# 14V2A.net
KiCad netlist of a schematic drawn in Altium Designer
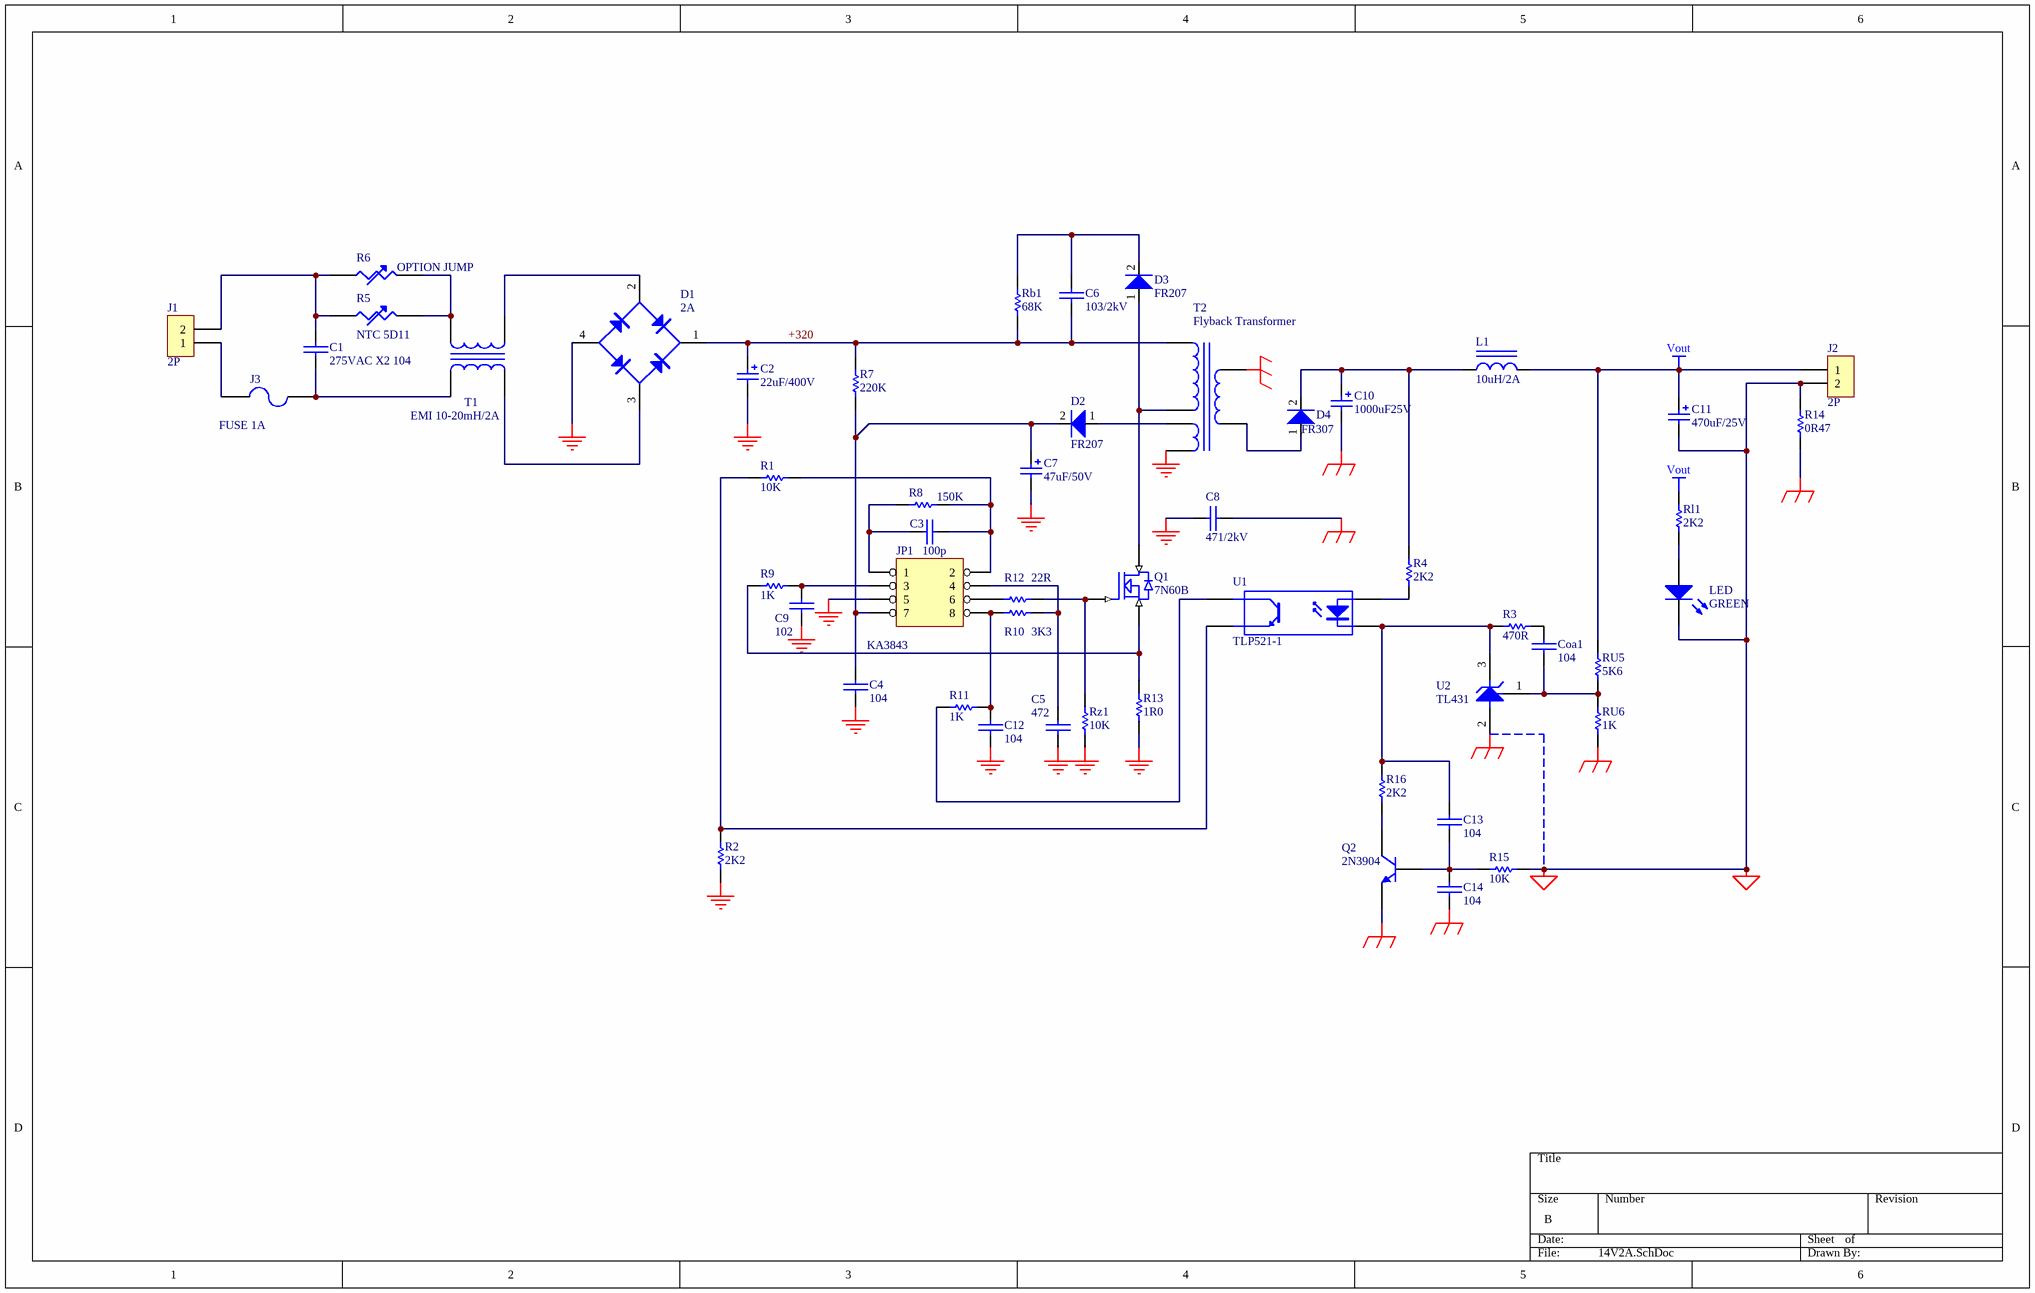
[diagram p0: 14V2A.SchDoc]

(export (version "E")
  (design (tool "Eeschema 10.0.6"))
  (components
    (comp (ref "C1")
      (value "275VAC X2 104")
      (footprint "100N400v")
      (fields (field (name "Comment") "Tụ điện chân cắm275VAC X2 104"))
      (libsource (lib "DnsSchLib") (part "CAP"))
    )
    (comp (ref "C2")
      (value "22uF/400V")
      (footprint "1000u50v")
      (description "Polarized Capacitor (Radial)")
      (fields (field (name "Comment") "Tụ hóa chân cắm22uF/400V") (field (name "PUBLISHER") "*"))
      (libsource (lib "DnsSchLib") (part "Cap Pol1"))
    )
    (comp (ref "C3")
      (value "100p")
      (footprint "0805C")
      (fields (field (name "Comment") "Tụ điện dán 0805100p"))
      (libsource (lib "DnsSchLib") (part "CAP"))
    )
    (comp (ref "C4")
      (value "104")
      (footprint "0805C")
      (fields (field (name "Comment") "Tụ điện dán 0805104"))
      (libsource (lib "DnsSchLib") (part "CAP"))
    )
    (comp (ref "C5")
      (value "472")
      (footprint "104nho")
      (fields (field (name "Comment") "Tụ điện chân cắm472"))
      (libsource (lib "DnsSchLib") (part "CAP"))
    )
    (comp (ref "C6")
      (value "103/2kV")
      (footprint "10n1000v")
      (fields (field (name "Comment") "Tụ điện chân cắm103/2kV"))
      (libsource (lib "DnsSchLib") (part "CAP"))
    )
    (comp (ref "C7")
      (value "47uF/50V")
      (footprint "10u50V")
      (description "Polarized Capacitor (Radial)")
      (fields (field (name "Comment") "Tụ hóa chân cắm47uF/50V") (field (name "PUBLISHER") "*"))
      (libsource (lib "DnsSchLib") (part "Cap Pol1"))
    )
    (comp (ref "C8")
      (value "471/2kV")
      (footprint "10n1000v")
      (fields (field (name "Comment") "Tụ điện chân cắm471/2kV"))
      (libsource (lib "DnsSchLib") (part "CAP"))
    )
    (comp (ref "C9")
      (value "102")
      (footprint "0805C")
      (fields (field (name "Comment") "Tụ điện dán 0805102"))
      (libsource (lib "DnsSchLib") (part "CAP"))
    )
    (comp (ref "C10")
      (value "1000uF25V")
      (footprint "1000u16v")
      (description "Polarized Capacitor (Radial)")
      (fields (field (name "Comment") "Tụ hóa chân cắm1000uF25V") (field (name "PUBLISHER") "*"))
      (libsource (lib "DnsSchLib") (part "Cap Pol1"))
    )
    (comp (ref "C11")
      (value "470uF/25V")
      (footprint "1000u16v")
      (description "Polarized Capacitor (Radial)")
      (fields (field (name "Comment") "Tụ hóa chân cắm470uF/25V") (field (name "PUBLISHER") "*"))
      (libsource (lib "DnsSchLib") (part "Cap Pol1"))
    )
    (comp (ref "C12")
      (value "104")
      (footprint "0805C")
      (fields (field (name "Comment") "Tụ điện dán 0805104"))
      (libsource (lib "DnsSchLib") (part "CAP"))
    )
    (comp (ref "C13")
      (value "104")
      (footprint "0805C")
      (fields (field (name "Comment") "Tụ điện dán 0805104"))
      (libsource (lib "DnsSchLib") (part "CAP"))
    )
    (comp (ref "C14")
      (value "104")
      (footprint "0805C")
      (fields (field (name "Comment") "Tụ điện dán 0805104"))
      (libsource (lib "DnsSchLib") (part "CAP"))
    )
    (comp (ref "Coa1")
      (value "104")
      (footprint "0805C")
      (fields (field (name "Comment") "Tụ điện dán 0805104"))
      (libsource (lib "DnsSchLib") (part "CAP"))
    )
    (comp (ref "D1")
      (value "2A")
      (footprint "Cau2a")
      (description "Diode Bridge")
      (fields (field (name "Comment") "Cầu chỉnh lưu Diode dẹt, chân cắm2A"))
      (libsource (lib "DnsSchLib") (part "BRIDGE1"))
    )
    (comp (ref "D2")
      (value "FR207")
      (footprint "DIODE1A")
      (fields (field (name "Comment") "Diode xung chân cắm 2AFR207"))
      (libsource (lib "DnsSchLib") (part "DIODE"))
    )
    (comp (ref "D3")
      (value "FR207")
      (footprint "DIODE1A")
      (fields (field (name "Comment") "Diode xung chân cắm 2AFR207"))
      (libsource (lib "DnsSchLib") (part "DIODE"))
    )
    (comp (ref "D4")
      (value "FR307")
      (footprint "1N5408")
      (fields (field (name "Comment") "Diode xung chân cắm 3AFR307"))
      (libsource (lib "DnsSchLib") (part "DIODE"))
    )
    (comp (ref "J1")
      (value "2P")
      (footprint "jack2_nam")
      (fields (field (name "Comment") "Jump đực loại thẳng, 2.54mm2P"))
      (libsource (lib "DnsSchLib") (part "CON2"))
    )
    (comp (ref "J2")
      (value "2P")
      (footprint "jack2_nam")
      (fields (field (name "Comment") "Jump đực loại thẳng, 2.54mm2P"))
      (libsource (lib "") (part "CON2_1"))
    )
    (comp (ref "J3")
      (value "FUSE 1A")
      (footprint "R2W_DUNG")
      (description "Fuse")
      (fields (field (name "Comment") "Cầu chì 1A/275V"))
      (libsource (lib "*") (part "FUSE2"))
    )
    (comp (ref "JP1")
      (value "KA3843")
      (footprint "DIP8")
      (fields (field (name "Comment") "IC điều khiển nguồn AC-DC KA3843"))
      (libsource (lib "*") (part "HEADER 4X2"))
    )
    (comp (ref "L1")
      (value "10uH/2A")
      (footprint "330uH")
      (fields (field (name "Comment") "Cuộn cảm chân cắm lõi trụ10uH/2A"))
      (libsource (lib "DnsSchLib") (part "INDUCTORSMALL"))
    )
    (comp (ref "LED")
      (value "GREEN")
      (footprint "LED0805")
      (description "Typical INFRARED GaAs LED")
      (fields (field (name "Comment") "LED dán 0805GREEN") (field (name "PUBLISHER") "*"))
      (libsource (lib "DnsSchLib") (part "LED0"))
    )
    (comp (ref "Q1")
      (value "7N60B")
      (footprint "TO220TNB")
      (fields (field (name "Comment") "Transistor trường MOSFET N, chân cắm TO-2207N60B"))
      (libsource (lib "DnsSchLib") (part "MOSFET N"))
    )
    (comp (ref "Q2")
      (value "2N3904")
      (footprint "SOT23S")
      (description "NPN Bipolar Transistor")
      (fields
        (field (name "Comment") "Transistor BJT NPN, chân dán SOT-232N3904")
        (field (name "PUBLISHER") "*")
      )
      (libsource (lib "DnsSchLib") (part "NPN"))
    )
    (comp (ref "R1")
      (value "10K")
      (footprint "0805DD")
      (description "Semiconductor Resistor")
      (fields (field (name "Comment") "Điện trở dán 080510K") (field (name "PUBLISHER") "*"))
      (libsource (lib "DnsSchLib") (part "Res Semi"))
    )
    (comp (ref "R2")
      (value "2K2")
      (footprint "0805DD")
      (description "Semiconductor Resistor")
      (fields (field (name "Comment") "Điện trở dán 08052K2") (field (name "PUBLISHER") "*"))
      (libsource (lib "DnsSchLib") (part "Res Semi"))
    )
    (comp (ref "R3")
      (value "470R")
      (footprint "0805DD")
      (description "Semiconductor Resistor")
      (fields (field (name "Comment") "Điện trở dán 0805470R") (field (name "PUBLISHER") "*"))
      (libsource (lib "DnsSchLib") (part "Res Semi"))
    )
    (comp (ref "R4")
      (value "2K2")
      (footprint "0805DD")
      (description "Semiconductor Resistor")
      (fields (field (name "Comment") "Điện trở dán 08052K2") (field (name "PUBLISHER") "*"))
      (libsource (lib "DnsSchLib") (part "Res Semi"))
    )
    (comp (ref "R5")
      (value "NTC 5D11")
      (footprint "CSIP4")
      (fields (field (name "Comment") "Nhiệt điện trở âm NTC 5D11"))
      (libsource (lib "*") (part "RES3"))
    )
    (comp (ref "R6") (value "OPTION JUMP") (footprint "XPAD") (libsource (lib "*") (part "RES3")))
    (comp (ref "R7")
      (value "220K")
      (footprint "R2W_DUNG")
      (description "Semiconductor Resistor")
      (fields (field (name "Comment") "Điện trở chân cắm 2W220K") (field (name "PUBLISHER") "*"))
      (libsource (lib "DnsSchLib") (part "Res Semi"))
    )
    (comp (ref "R8")
      (value "150K")
      (footprint "0805DD")
      (description "Semiconductor Resistor")
      (fields (field (name "Comment") "Điện trở dán 0805150K") (field (name "PUBLISHER") "*"))
      (libsource (lib "DnsSchLib") (part "Res Semi"))
    )
    (comp (ref "R9")
      (value "1K")
      (footprint "0805DD")
      (description "Semiconductor Resistor")
      (fields (field (name "Comment") "Điện trở dán 08051K") (field (name "PUBLISHER") "*"))
      (libsource (lib "DnsSchLib") (part "Res Semi"))
    )
    (comp (ref "R10")
      (value "3K3")
      (footprint "0805DD")
      (description "Semiconductor Resistor")
      (fields (field (name "Comment") "Điện trở dán 08053K3") (field (name "PUBLISHER") "*"))
      (libsource (lib "DnsSchLib") (part "Res Semi"))
    )
    (comp (ref "R11")
      (value "1K")
      (footprint "0805DD")
      (description "Semiconductor Resistor")
      (fields (field (name "Comment") "Điện trở dán 08051K") (field (name "PUBLISHER") "*"))
      (libsource (lib "DnsSchLib") (part "Res Semi"))
    )
    (comp (ref "R12")
      (value "22R")
      (footprint "0805DD")
      (description "Semiconductor Resistor")
      (fields (field (name "Comment") "Điện trở dán 080522R") (field (name "PUBLISHER") "*"))
      (libsource (lib "DnsSchLib") (part "Res Semi"))
    )
    (comp (ref "R13")
      (value "1R0")
      (footprint "R2WDUNG")
      (description "Semiconductor Resistor")
      (fields (field (name "Comment") "Điện trở chân cắm 2W1R0") (field (name "PUBLISHER") "*"))
      (libsource (lib "DnsSchLib") (part "Res Semi"))
    )
    (comp (ref "R14")
      (value "0R47")
      (footprint "R2WDUNG")
      (description "Semiconductor Resistor")
      (fields (field (name "Comment") "Điện trở chân cắm 2W0R47") (field (name "PUBLISHER") "*"))
      (libsource (lib "DnsSchLib") (part "Res Semi"))
    )
    (comp (ref "R15")
      (value "10K")
      (footprint "0805DD")
      (description "Semiconductor Resistor")
      (fields (field (name "Comment") "Điện trở dán 080510K") (field (name "PUBLISHER") "*"))
      (libsource (lib "DnsSchLib") (part "Res Semi"))
    )
    (comp (ref "R16")
      (value "2K2")
      (footprint "0805DD")
      (description "Semiconductor Resistor")
      (fields (field (name "Comment") "Điện trở dán 08052K2") (field (name "PUBLISHER") "*"))
      (libsource (lib "DnsSchLib") (part "Res Semi"))
    )
    (comp (ref "Rb1")
      (value "68K")
      (footprint "AXIAL0.4")
      (description "Semiconductor Resistor")
      (fields (field (name "Comment") "Điện trở chân cắm 1W68K") (field (name "PUBLISHER") "*"))
      (libsource (lib "DnsSchLib") (part "Res Semi"))
    )
    (comp (ref "Rl1")
      (value "2K2")
      (footprint "0805DD")
      (description "Semiconductor Resistor")
      (fields (field (name "Comment") "Điện trở dán 08052K2") (field (name "PUBLISHER") "*"))
      (libsource (lib "DnsSchLib") (part "Res Semi"))
    )
    (comp (ref "RU5")
      (value "5K6")
      (footprint "0805DD")
      (description "Semiconductor Resistor")
      (fields (field (name "Comment") "Điện trở dán 08055K6") (field (name "PUBLISHER") "*"))
      (libsource (lib "DnsSchLib") (part "Res Semi"))
    )
    (comp (ref "RU6")
      (value "1K")
      (footprint "0805DD")
      (description "Semiconductor Resistor")
      (fields (field (name "Comment") "Điện trở dán 08051K") (field (name "PUBLISHER") "*"))
      (libsource (lib "DnsSchLib") (part "Res Semi"))
    )
    (comp (ref "Rz1")
      (value "10K")
      (footprint "0805DD")
      (description "Semiconductor Resistor")
      (fields (field (name "Comment") "Điện trở dán 080510K") (field (name "PUBLISHER") "*"))
      (libsource (lib "DnsSchLib") (part "Res Semi"))
    )
    (comp (ref "T1")
      (value "EMI 10-20mH/2A")
      (footprint "EMI_Filter")
      (fields (field (name "Comment") "Cuộn cảm lọc đầu vào EMI Filter 10-20mH/2A"))
      (libsource (lib "*") (part "TRANS1"))
    )
    (comp (ref "T2")
      (value "Flyback Transformer")
      (footprint "Trans6c")
      (fields (field (name "Comment") "Biến áp xung Flyback"))
      (libsource (lib "*") (part "TRANS6"))
    )
    (comp (ref "U1")
      (value "TLP521-1")
      (footprint "TLP521_1")
      (description "Optoisolator")
      (fields (field (name "Comment") "Cách ly quang chân cắmTLP521-1"))
      (libsource (lib "DnsSchLib") (part "OPTOISO1"))
    )
    (comp (ref "U2")
      (value "TL431")
      (footprint "TO92_431")
      (description "Adjustable Precision Shunt Regulator")
      (fields (field (name "Comment") "IC điện áp chuẩn, chân cắm TO92TL431"))
      (libsource (lib "DnsSchLib") (part "TL431"))
    )
  )
  (nets
    (net (code "1") (name "/+320") (class "Default")
      (node (ref "C2") (pin "1") (pinfunction "1_1") (pintype "passive"))
      (node (ref "C6") (pin "2") (pinfunction "2_2") (pintype "passive"))
      (node (ref "D1") (pin "1") (pinfunction "V+_1") (pintype "passive"))
      (node (ref "R7") (pin "2") (pinfunction "2_2") (pintype "passive"))
      (node (ref "Rb1") (pin "2") (pinfunction "2_2") (pintype "passive"))
      (node (ref "T2") (pin "1") (pinfunction "1_1") (pintype "passive"))
    )
    (net (code "2") (name "EARTH") (class "Default")
      (node (ref "C10") (pin "2") (pinfunction "2_2") (pintype "passive"))
      (node (ref "C14") (pin "2") (pinfunction "2_2") (pintype "passive"))
      (node (ref "C8") (pin "2") (pinfunction "2_2") (pintype "passive"))
      (node (ref "Q2") (pin "3") (pinfunction "E_3") (pintype "passive"))
      (node (ref "R14") (pin "1") (pinfunction "1_1") (pintype "passive"))
      (node (ref "RU6") (pin "2") (pinfunction "2_2") (pintype "passive"))
      (node (ref "T2") (pin "5") (pinfunction "5_5") (pintype "passive"))
      (node (ref "U2") (pin "2") (pinfunction "A_2") (pintype "passive"))
    )
    (net (code "3") (name "EARTH2") (class "Default")
      (node (ref "C11") (pin "2") (pinfunction "2_2") (pintype "passive"))
      (node (ref "J2") (pin "2") (pinfunction "2_2") (pintype "passive"))
      (node (ref "LED") (pin "2") (pinfunction "K_2") (pintype "passive"))
      (node (ref "R14") (pin "2") (pinfunction "2_2") (pintype "passive"))
      (node (ref "R15") (pin "2") (pinfunction "2_2") (pintype "passive"))
    )
    (net (code "4") (name "GND") (class "Default")
      (node (ref "C12") (pin "2") (pinfunction "2_2") (pintype "passive"))
      (node (ref "C2") (pin "2") (pinfunction "2_2") (pintype "passive"))
      (node (ref "C4") (pin "2") (pinfunction "2_2") (pintype "passive"))
      (node (ref "C5") (pin "1") (pinfunction "1_1") (pintype "passive"))
      (node (ref "C7") (pin "2") (pinfunction "2_2") (pintype "passive"))
      (node (ref "C8") (pin "1") (pinfunction "1_1") (pintype "passive"))
      (node (ref "C9") (pin "2") (pinfunction "2_2") (pintype "passive"))
      (node (ref "D1") (pin "4") (pinfunction "V-_4") (pintype "passive"))
      (node (ref "JP1") (pin "5") (pinfunction "5_5") (pintype "passive"))
      (node (ref "R13") (pin "2") (pinfunction "2_2") (pintype "passive"))
      (node (ref "R2") (pin "2") (pinfunction "2_2") (pintype "passive"))
      (node (ref "Rz1") (pin "2") (pinfunction "2_2") (pintype "passive"))
      (node (ref "T2") (pin "4") (pinfunction "4_4") (pintype "passive"))
    )
    (net (code "5") (name "Net-(C1-Pad1)") (class "Default")
      (node (ref "C1") (pin "1") (pinfunction "1_1") (pintype "passive"))
      (node (ref "J3") (pin "2") (pinfunction "2_2") (pintype "passive"))
      (node (ref "T1") (pin "1") (pinfunction "1_1") (pintype "passive"))
    )
    (net (code "6") (name "Net-(C1-Pad2)") (class "Default")
      (node (ref "C1") (pin "2") (pinfunction "2_2") (pintype "passive"))
      (node (ref "J1") (pin "2") (pinfunction "2_2") (pintype "passive"))
      (node (ref "R5") (pin "1") (pinfunction "1_1") (pintype "passive"))
      (node (ref "R6") (pin "1") (pinfunction "1_1") (pintype "passive"))
    )
    (net (code "7") (name "Net-(C3-Pad1)") (class "Default")
      (node (ref "C3") (pin "1") (pinfunction "1_1") (pintype "passive"))
      (node (ref "JP1") (pin "1") (pinfunction "1_1") (pintype "passive"))
      (node (ref "R8") (pin "1") (pinfunction "1_1") (pintype "passive"))
    )
    (net (code "8") (name "Net-(C3-Pad2)") (class "Default")
      (node (ref "C3") (pin "2") (pinfunction "2_2") (pintype "passive"))
      (node (ref "JP1") (pin "2") (pinfunction "2_2") (pintype "passive"))
      (node (ref "R1") (pin "2") (pinfunction "2_2") (pintype "passive"))
      (node (ref "R8") (pin "2") (pinfunction "2_2") (pintype "passive"))
    )
    (net (code "9") (name "Net-(C5-Pad2)") (class "Default")
      (node (ref "C5") (pin "2") (pinfunction "2_2") (pintype "passive"))
      (node (ref "JP1") (pin "4") (pinfunction "4_4") (pintype "passive"))
      (node (ref "R10") (pin "2") (pinfunction "2_2") (pintype "passive"))
    )
    (net (code "10") (name "Net-(C9-Pad1)") (class "Default")
      (node (ref "C9") (pin "1") (pinfunction "1_1") (pintype "passive"))
      (node (ref "JP1") (pin "3") (pinfunction "3_3") (pintype "passive"))
      (node (ref "R9") (pin "1") (pinfunction "1_1") (pintype "passive"))
    )
    (net (code "11") (name "Net-(C12-Pad1)") (class "Default")
      (node (ref "C12") (pin "1") (pinfunction "1_1") (pintype "passive"))
      (node (ref "JP1") (pin "8") (pinfunction "8_8") (pintype "passive"))
      (node (ref "R10") (pin "1") (pinfunction "1_1") (pintype "passive"))
      (node (ref "R11") (pin "1") (pinfunction "1_1") (pintype "passive"))
    )
    (net (code "12") (name "Net-(Coa1-Pad1)") (class "Default")
      (node (ref "Coa1") (pin "1") (pinfunction "1_1") (pintype "passive"))
      (node (ref "R3") (pin "1") (pinfunction "1_1") (pintype "passive"))
    )
    (net (code "13") (name "Net-(D1-AC-Pad2)") (class "Default")
      (node (ref "D1") (pin "2") (pinfunction "AC_2") (pintype "passive"))
      (node (ref "T1") (pin "4") (pinfunction "4_4") (pintype "passive"))
    )
    (net (code "14") (name "Net-(D1-AC-Pad3)") (class "Default")
      (node (ref "D1") (pin "3") (pinfunction "AC_3") (pintype "passive"))
      (node (ref "T1") (pin "3") (pinfunction "3_3") (pintype "passive"))
    )
    (net (code "15") (name "Net-(D2-A)") (class "Default")
      (node (ref "D2") (pin "1") (pinfunction "A_1") (pintype "passive"))
      (node (ref "T2") (pin "3") (pinfunction "3_3") (pintype "passive"))
    )
    (net (code "16") (name "Net-(D2-K)") (class "Default")
      (node (ref "C4") (pin "1") (pinfunction "1_1") (pintype "passive"))
      (node (ref "C7") (pin "1") (pinfunction "1_1") (pintype "passive"))
      (node (ref "D2") (pin "2") (pinfunction "K_2") (pintype "passive"))
      (node (ref "JP1") (pin "7") (pinfunction "7_7") (pintype "passive"))
      (node (ref "R7") (pin "1") (pinfunction "1_1") (pintype "passive"))
    )
    (net (code "17") (name "Net-(D3-A)") (class "Default")
      (node (ref "D3") (pin "1") (pinfunction "A_1") (pintype "passive"))
      (node (ref "Q1") (pin "2") (pinfunction "D_2") (pintype "input"))
      (node (ref "T2") (pin "2") (pinfunction "2_2") (pintype "passive"))
    )
    (net (code "18") (name "Net-(D3-K)") (class "Default")
      (node (ref "C6") (pin "1") (pinfunction "1_1") (pintype "passive"))
      (node (ref "D3") (pin "2") (pinfunction "K_2") (pintype "passive"))
      (node (ref "Rb1") (pin "1") (pinfunction "1_1") (pintype "passive"))
    )
    (net (code "19") (name "Net-(D4-A)") (class "Default")
      (node (ref "D4") (pin "1") (pinfunction "A_1") (pintype "passive"))
      (node (ref "T2") (pin "6") (pinfunction "6_6") (pintype "passive"))
    )
    (net (code "20") (name "Net-(D4-K)") (class "Default")
      (node (ref "C10") (pin "1") (pinfunction "1_1") (pintype "passive"))
      (node (ref "D4") (pin "2") (pinfunction "K_2") (pintype "passive"))
      (node (ref "L1") (pin "1") (pinfunction "1_1") (pintype "passive"))
      (node (ref "R4") (pin "2") (pinfunction "2_2") (pintype "passive"))
    )
    (net (code "21") (name "Net-(J1-Pad1)") (class "Default")
      (node (ref "J1") (pin "1") (pinfunction "1_1") (pintype "passive"))
      (node (ref "J3") (pin "1") (pinfunction "1_1") (pintype "passive"))
    )
    (net (code "22") (name "Net-(JP1-Pad6)") (class "Default")
      (node (ref "JP1") (pin "6") (pinfunction "6_6") (pintype "passive"))
      (node (ref "R12") (pin "1") (pinfunction "1_1") (pintype "passive"))
    )
    (net (code "23") (name "Net-(LED-A)") (class "Default")
      (node (ref "LED") (pin "1") (pinfunction "A_1") (pintype "passive"))
      (node (ref "Rl1") (pin "2") (pinfunction "2_2") (pintype "passive"))
    )
    (net (code "24") (name "Net-(Q1-G)") (class "Default")
      (node (ref "Q1") (pin "1") (pinfunction "G_1") (pintype "input"))
      (node (ref "R12") (pin "2") (pinfunction "2_2") (pintype "passive"))
      (node (ref "Rz1") (pin "1") (pinfunction "1_1") (pintype "passive"))
    )
    (net (code "25") (name "Net-(Q1-S)") (class "Default")
      (node (ref "Q1") (pin "3") (pinfunction "S_3") (pintype "input"))
      (node (ref "R13") (pin "1") (pinfunction "1_1") (pintype "passive"))
      (node (ref "R9") (pin "2") (pinfunction "2_2") (pintype "passive"))
    )
    (net (code "26") (name "Net-(Q2-B)") (class "Default")
      (node (ref "C13") (pin "1") (pinfunction "1_1") (pintype "passive"))
      (node (ref "C14") (pin "1") (pinfunction "1_1") (pintype "passive"))
      (node (ref "Q2") (pin "1") (pinfunction "B_1") (pintype "passive"))
      (node (ref "R15") (pin "1") (pinfunction "1_1") (pintype "passive"))
    )
    (net (code "27") (name "Net-(Q2-C)") (class "Default")
      (node (ref "Q2") (pin "2") (pinfunction "C_2") (pintype "passive"))
      (node (ref "R16") (pin "1") (pinfunction "1_1") (pintype "passive"))
    )
    (net (code "28") (name "Net-(R5-Pad2)") (class "Default")
      (node (ref "R5") (pin "2") (pinfunction "2_2") (pintype "passive"))
      (node (ref "R6") (pin "2") (pinfunction "2_2") (pintype "passive"))
      (node (ref "T1") (pin "2") (pinfunction "2_2") (pintype "passive"))
    )
    (net (code "29") (name "Net-(U1-A)") (class "Default")
      (node (ref "R4") (pin "1") (pinfunction "1_1") (pintype "passive"))
      (node (ref "U1") (pin "1") (pinfunction "A_1") (pintype "passive"))
    )
    (net (code "30") (name "Net-(U1-C)") (class "Default")
      (node (ref "R1") (pin "1") (pinfunction "1_1") (pintype "passive"))
      (node (ref "R2") (pin "1") (pinfunction "1_1") (pintype "passive"))
      (node (ref "U1") (pin "3") (pinfunction "C_3") (pintype "passive"))
    )
    (net (code "31") (name "Net-(U1-E)") (class "Default")
      (node (ref "R11") (pin "2") (pinfunction "2_2") (pintype "passive"))
      (node (ref "U1") (pin "4") (pinfunction "E_4") (pintype "passive"))
    )
    (net (code "32") (name "Net-(U1-K)") (class "Default")
      (node (ref "C13") (pin "2") (pinfunction "2_2") (pintype "passive"))
      (node (ref "R16") (pin "2") (pinfunction "2_2") (pintype "passive"))
      (node (ref "R3") (pin "2") (pinfunction "2_2") (pintype "passive"))
      (node (ref "U1") (pin "2") (pinfunction "K_2") (pintype "passive"))
      (node (ref "U2") (pin "3") (pinfunction "K_3") (pintype "passive"))
    )
    (net (code "33") (name "Net-(U2-R)") (class "Default")
      (node (ref "Coa1") (pin "2") (pinfunction "2_2") (pintype "passive"))
      (node (ref "RU5") (pin "2") (pinfunction "2_2") (pintype "passive"))
      (node (ref "RU6") (pin "1") (pinfunction "1_1") (pintype "passive"))
      (node (ref "U2") (pin "1") (pinfunction "R_1") (pintype "passive"))
    )
    (net (code "34") (name "Vout") (class "Default")
      (node (ref "C11") (pin "1") (pinfunction "1_1") (pintype "passive"))
      (node (ref "J2") (pin "1") (pinfunction "1_1") (pintype "passive"))
      (node (ref "L1") (pin "2") (pinfunction "2_2") (pintype "passive"))
      (node (ref "RU5") (pin "1") (pinfunction "1_1") (pintype "passive"))
      (node (ref "Rl1") (pin "1") (pinfunction "1_1") (pintype "passive"))
    )
  )
)
